# 6waydistro.net
KiCad netlist of a schematic drawn in EAGLE
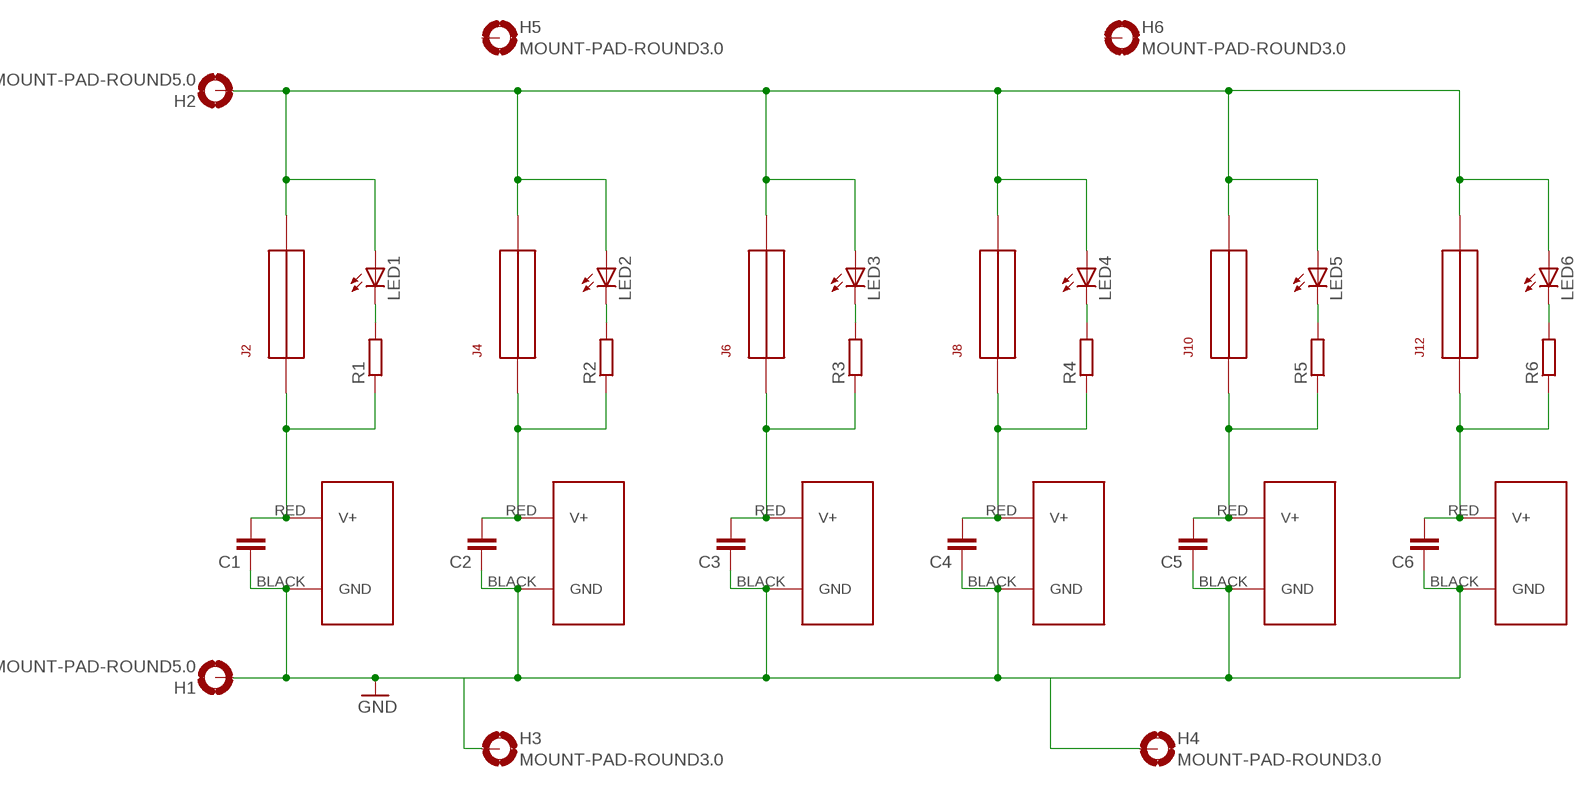
[diagram p0: schematic, sheet 1]

(export (version "E")
  (design (tool "Eeschema 10.0.6"))
  (components
    (comp (ref "C1")
      (value "C-EU050-025X075")
      (footprint "eagle-import:C050-025X075")
      (libsource (lib "eagle-import") (part "C-EU050-025X075"))
    )
    (comp (ref "C2")
      (value "C-EU050-025X075")
      (footprint "eagle-import:C050-025X075")
      (libsource (lib "eagle-import") (part "C-EU050-025X075"))
    )
    (comp (ref "C3")
      (value "C-EU050-025X075")
      (footprint "eagle-import:C050-025X075")
      (libsource (lib "eagle-import") (part "C-EU050-025X075"))
    )
    (comp (ref "C4")
      (value "C-EU050-025X075")
      (footprint "eagle-import:C050-025X075")
      (libsource (lib "eagle-import") (part "C-EU050-025X075"))
    )
    (comp (ref "C5")
      (value "C-EU050-025X075")
      (footprint "eagle-import:C050-025X075")
      (libsource (lib "eagle-import") (part "C-EU050-025X075"))
    )
    (comp (ref "C6")
      (value "C-EU050-025X075")
      (footprint "eagle-import:C050-025X075")
      (libsource (lib "eagle-import") (part "C-EU050-025X075"))
    )
    (comp (ref "H1")
      (value "MOUNT-PAD-ROUND5.0")
      (footprint "eagle-import:5,0-PAD")
      (libsource (lib "eagle-import") (part "MOUNT-PAD-ROUND5.0"))
    )
    (comp (ref "H2")
      (value "MOUNT-PAD-ROUND5.0")
      (footprint "eagle-import:5,0-PAD")
      (libsource (lib "eagle-import") (part "MOUNT-PAD-ROUND5.0"))
    )
    (comp (ref "H3")
      (value "MOUNT-PAD-ROUND3.0")
      (footprint "eagle-import:3,0-PAD")
      (libsource (lib "eagle-import") (part "MOUNT-PAD-ROUND3.0"))
    )
    (comp (ref "H4")
      (value "MOUNT-PAD-ROUND3.0")
      (footprint "eagle-import:3,0-PAD")
      (libsource (lib "eagle-import") (part "MOUNT-PAD-ROUND3.0"))
    )
    (comp (ref "H5")
      (value "MOUNT-PAD-ROUND3.0")
      (footprint "eagle-import:3,0-PAD")
      (libsource (lib "eagle-import") (part "MOUNT-PAD-ROUND3.0"))
    )
    (comp (ref "H6")
      (value "MOUNT-PAD-ROUND3.0")
      (footprint "eagle-import:3,0-PAD")
      (libsource (lib "eagle-import") (part "MOUNT-PAD-ROUND3.0"))
    )
    (comp (ref "J1")
      (value "POWERPOLE_POWER10AWG")
      (footprint "eagle-import:POWERPOLE_PAIR_10AWG")
      (libsource (lib "eagle-import") (part "POWERPOLE_POWER10AWG"))
    )
    (comp (ref "J2")
      (value "FUSEATC")
      (footprint "eagle-import:FUSE_ATC")
      (libsource (lib "eagle-import") (part "FUSEATC"))
    )
    (comp (ref "J3")
      (value "POWERPOLE_POWER10AWG")
      (footprint "eagle-import:POWERPOLE_PAIR_10AWG")
      (libsource (lib "eagle-import") (part "POWERPOLE_POWER10AWG"))
    )
    (comp (ref "J4")
      (value "FUSEATC")
      (footprint "eagle-import:FUSE_ATC")
      (libsource (lib "eagle-import") (part "FUSEATC"))
    )
    (comp (ref "J5")
      (value "POWERPOLE_POWER10AWG")
      (footprint "eagle-import:POWERPOLE_PAIR_10AWG")
      (libsource (lib "eagle-import") (part "POWERPOLE_POWER10AWG"))
    )
    (comp (ref "J6")
      (value "FUSEATC")
      (footprint "eagle-import:FUSE_ATC")
      (libsource (lib "eagle-import") (part "FUSEATC"))
    )
    (comp (ref "J7")
      (value "POWERPOLE_POWER10AWG")
      (footprint "eagle-import:POWERPOLE_PAIR_10AWG")
      (libsource (lib "eagle-import") (part "POWERPOLE_POWER10AWG"))
    )
    (comp (ref "J8")
      (value "FUSEATC")
      (footprint "eagle-import:FUSE_ATC")
      (libsource (lib "eagle-import") (part "FUSEATC"))
    )
    (comp (ref "J9")
      (value "POWERPOLE_POWER10AWG")
      (footprint "eagle-import:POWERPOLE_PAIR_10AWG")
      (libsource (lib "eagle-import") (part "POWERPOLE_POWER10AWG"))
    )
    (comp (ref "J10")
      (value "FUSEATC")
      (footprint "eagle-import:FUSE_ATC")
      (libsource (lib "eagle-import") (part "FUSEATC"))
    )
    (comp (ref "J11")
      (value "POWERPOLE_POWER10AWG")
      (footprint "eagle-import:POWERPOLE_PAIR_10AWG")
      (libsource (lib "eagle-import") (part "POWERPOLE_POWER10AWG"))
    )
    (comp (ref "J12")
      (value "FUSEATC")
      (footprint "eagle-import:FUSE_ATC")
      (libsource (lib "eagle-import") (part "FUSEATC"))
    )
    (comp (ref "LED1")
      (value "LED3MM")
      (footprint "eagle-import:LED3MM")
      (libsource (lib "eagle-import") (part "LED3MM"))
    )
    (comp (ref "LED2")
      (value "LED3MM")
      (footprint "eagle-import:LED3MM")
      (libsource (lib "eagle-import") (part "LED3MM"))
    )
    (comp (ref "LED3")
      (value "LED3MM")
      (footprint "eagle-import:LED3MM")
      (libsource (lib "eagle-import") (part "LED3MM"))
    )
    (comp (ref "LED4")
      (value "LED3MM")
      (footprint "eagle-import:LED3MM")
      (libsource (lib "eagle-import") (part "LED3MM"))
    )
    (comp (ref "LED5")
      (value "LED3MM")
      (footprint "eagle-import:LED3MM")
      (libsource (lib "eagle-import") (part "LED3MM"))
    )
    (comp (ref "LED6")
      (value "LED3MM")
      (footprint "eagle-import:LED3MM")
      (libsource (lib "eagle-import") (part "LED3MM"))
    )
    (comp (ref "R1")
      (value "R-EU_0204/7")
      (footprint "eagle-import:0204_7")
      (libsource (lib "eagle-import") (part "R-EU_0204/7"))
    )
    (comp (ref "R2")
      (value "R-EU_0204/7")
      (footprint "eagle-import:0204_7")
      (libsource (lib "eagle-import") (part "R-EU_0204/7"))
    )
    (comp (ref "R3")
      (value "R-EU_0204/7")
      (footprint "eagle-import:0204_7")
      (libsource (lib "eagle-import") (part "R-EU_0204/7"))
    )
    (comp (ref "R4")
      (value "R-EU_0204/7")
      (footprint "eagle-import:0204_7")
      (libsource (lib "eagle-import") (part "R-EU_0204/7"))
    )
    (comp (ref "R5")
      (value "R-EU_0204/7")
      (footprint "eagle-import:0204_7")
      (libsource (lib "eagle-import") (part "R-EU_0204/7"))
    )
    (comp (ref "R6")
      (value "R-EU_0204/7")
      (footprint "eagle-import:0204_7")
      (libsource (lib "eagle-import") (part "R-EU_0204/7"))
    )
  )
  (nets
    (net (code "1") (name "GND") (class "Default")
      (node (ref "C1") (pin "1") (pinfunction "1_1") (pintype "passive"))
      (node (ref "C2") (pin "1") (pinfunction "1_1") (pintype "passive"))
      (node (ref "C3") (pin "1") (pinfunction "1_1") (pintype "passive"))
      (node (ref "C4") (pin "1") (pinfunction "1_1") (pintype "passive"))
      (node (ref "C5") (pin "1") (pinfunction "1_1") (pintype "passive"))
      (node (ref "C6") (pin "1") (pinfunction "1_1") (pintype "passive"))
      (node (ref "H1") (pin "B5") (pinfunction "MOUNT_B5") (pintype "passive"))
      (node (ref "H3") (pin "B3,0") (pinfunction "MOUNT_B3,0") (pintype "passive"))
      (node (ref "H4") (pin "B3,0") (pinfunction "MOUNT_B3,0") (pintype "passive"))
      (node (ref "J1") (pin "BLACK") (pinfunction "GND_BLACK") (pintype "power_in"))
      (node (ref "J11") (pin "BLACK") (pinfunction "GND_BLACK") (pintype "power_in"))
      (node (ref "J3") (pin "BLACK") (pinfunction "GND_BLACK") (pintype "power_in"))
      (node (ref "J5") (pin "BLACK") (pinfunction "GND_BLACK") (pintype "power_in"))
      (node (ref "J7") (pin "BLACK") (pinfunction "GND_BLACK") (pintype "power_in"))
      (node (ref "J9") (pin "BLACK") (pinfunction "GND_BLACK") (pintype "power_in"))
    )
    (net (code "2") (name "Net-(H2-MOUNT)") (class "Default")
      (node (ref "H2") (pin "B5") (pinfunction "MOUNT_B5") (pintype "passive"))
      (node (ref "J10") (pin "P$3") (pinfunction "P$2_P$3") (pintype "bidirectional"))
      (node (ref "J10") (pin "P$4") (pinfunction "P$2_P$4") (pintype "bidirectional"))
      (node (ref "J12") (pin "P$3") (pinfunction "P$2_P$3") (pintype "bidirectional"))
      (node (ref "J12") (pin "P$4") (pinfunction "P$2_P$4") (pintype "bidirectional"))
      (node (ref "J2") (pin "P$3") (pinfunction "P$2_P$3") (pintype "bidirectional"))
      (node (ref "J2") (pin "P$4") (pinfunction "P$2_P$4") (pintype "bidirectional"))
      (node (ref "J4") (pin "P$3") (pinfunction "P$2_P$3") (pintype "bidirectional"))
      (node (ref "J4") (pin "P$4") (pinfunction "P$2_P$4") (pintype "bidirectional"))
      (node (ref "J6") (pin "P$3") (pinfunction "P$2_P$3") (pintype "bidirectional"))
      (node (ref "J6") (pin "P$4") (pinfunction "P$2_P$4") (pintype "bidirectional"))
      (node (ref "J8") (pin "P$3") (pinfunction "P$2_P$3") (pintype "bidirectional"))
      (node (ref "J8") (pin "P$4") (pinfunction "P$2_P$4") (pintype "bidirectional"))
      (node (ref "LED1") (pin "A") (pinfunction "A_A") (pintype "passive"))
      (node (ref "LED2") (pin "A") (pinfunction "A_A") (pintype "passive"))
      (node (ref "LED3") (pin "A") (pinfunction "A_A") (pintype "passive"))
      (node (ref "LED4") (pin "A") (pinfunction "A_A") (pintype "passive"))
      (node (ref "LED5") (pin "A") (pinfunction "A_A") (pintype "passive"))
      (node (ref "LED6") (pin "A") (pinfunction "A_A") (pintype "passive"))
    )
    (net (code "3") (name "Net-(J1-V+)") (class "Default")
      (node (ref "C1") (pin "2") (pinfunction "2_2") (pintype "passive"))
      (node (ref "J1") (pin "RED") (pinfunction "V+_RED") (pintype "power_in"))
      (node (ref "J2") (pin "P$1") (pinfunction "P$1_P$1") (pintype "bidirectional"))
      (node (ref "J2") (pin "P$2") (pinfunction "P$1_P$2") (pintype "bidirectional"))
      (node (ref "R1") (pin "1") (pinfunction "1_1") (pintype "passive"))
    )
    (net (code "4") (name "Net-(J3-V+)") (class "Default")
      (node (ref "C2") (pin "2") (pinfunction "2_2") (pintype "passive"))
      (node (ref "J3") (pin "RED") (pinfunction "V+_RED") (pintype "power_in"))
      (node (ref "J4") (pin "P$1") (pinfunction "P$1_P$1") (pintype "bidirectional"))
      (node (ref "J4") (pin "P$2") (pinfunction "P$1_P$2") (pintype "bidirectional"))
      (node (ref "R2") (pin "1") (pinfunction "1_1") (pintype "passive"))
    )
    (net (code "5") (name "Net-(J5-V+)") (class "Default")
      (node (ref "C3") (pin "2") (pinfunction "2_2") (pintype "passive"))
      (node (ref "J5") (pin "RED") (pinfunction "V+_RED") (pintype "power_in"))
      (node (ref "J6") (pin "P$1") (pinfunction "P$1_P$1") (pintype "bidirectional"))
      (node (ref "J6") (pin "P$2") (pinfunction "P$1_P$2") (pintype "bidirectional"))
      (node (ref "R3") (pin "1") (pinfunction "1_1") (pintype "passive"))
    )
    (net (code "6") (name "Net-(J7-V+)") (class "Default")
      (node (ref "C4") (pin "2") (pinfunction "2_2") (pintype "passive"))
      (node (ref "J7") (pin "RED") (pinfunction "V+_RED") (pintype "power_in"))
      (node (ref "J8") (pin "P$1") (pinfunction "P$1_P$1") (pintype "bidirectional"))
      (node (ref "J8") (pin "P$2") (pinfunction "P$1_P$2") (pintype "bidirectional"))
      (node (ref "R4") (pin "1") (pinfunction "1_1") (pintype "passive"))
    )
    (net (code "7") (name "Net-(J9-V+)") (class "Default")
      (node (ref "C5") (pin "2") (pinfunction "2_2") (pintype "passive"))
      (node (ref "J10") (pin "P$1") (pinfunction "P$1_P$1") (pintype "bidirectional"))
      (node (ref "J10") (pin "P$2") (pinfunction "P$1_P$2") (pintype "bidirectional"))
      (node (ref "J9") (pin "RED") (pinfunction "V+_RED") (pintype "power_in"))
      (node (ref "R5") (pin "1") (pinfunction "1_1") (pintype "passive"))
    )
    (net (code "8") (name "Net-(J11-V+)") (class "Default")
      (node (ref "C6") (pin "2") (pinfunction "2_2") (pintype "passive"))
      (node (ref "J11") (pin "RED") (pinfunction "V+_RED") (pintype "power_in"))
      (node (ref "J12") (pin "P$1") (pinfunction "P$1_P$1") (pintype "bidirectional"))
      (node (ref "J12") (pin "P$2") (pinfunction "P$1_P$2") (pintype "bidirectional"))
      (node (ref "R6") (pin "1") (pinfunction "1_1") (pintype "passive"))
    )
    (net (code "9") (name "Net-(LED1-C)") (class "Default")
      (node (ref "LED1") (pin "K") (pinfunction "C_K") (pintype "passive"))
      (node (ref "R1") (pin "2") (pinfunction "2_2") (pintype "passive"))
    )
    (net (code "10") (name "Net-(LED2-C)") (class "Default")
      (node (ref "LED2") (pin "K") (pinfunction "C_K") (pintype "passive"))
      (node (ref "R2") (pin "2") (pinfunction "2_2") (pintype "passive"))
    )
    (net (code "11") (name "Net-(LED3-C)") (class "Default")
      (node (ref "LED3") (pin "K") (pinfunction "C_K") (pintype "passive"))
      (node (ref "R3") (pin "2") (pinfunction "2_2") (pintype "passive"))
    )
    (net (code "12") (name "Net-(LED4-C)") (class "Default")
      (node (ref "LED4") (pin "K") (pinfunction "C_K") (pintype "passive"))
      (node (ref "R4") (pin "2") (pinfunction "2_2") (pintype "passive"))
    )
    (net (code "13") (name "Net-(LED5-C)") (class "Default")
      (node (ref "LED5") (pin "K") (pinfunction "C_K") (pintype "passive"))
      (node (ref "R5") (pin "2") (pinfunction "2_2") (pintype "passive"))
    )
    (net (code "14") (name "Net-(LED6-C)") (class "Default")
      (node (ref "LED6") (pin "K") (pinfunction "C_K") (pintype "passive"))
      (node (ref "R6") (pin "2") (pinfunction "2_2") (pintype "passive"))
    )
    (net (code "15") (name "unconnected-(H5-MOUNT-PadB3,0)") (class "Default")
      (node (ref "H5") (pin "B3,0") (pinfunction "MOUNT_B3,0") (pintype "passive"))
    )
    (net (code "16") (name "unconnected-(H6-MOUNT-PadB3,0)") (class "Default")
      (node (ref "H6") (pin "B3,0") (pinfunction "MOUNT_B3,0") (pintype "passive"))
    )
  )
)
